# Power.net
KiCad netlist of a schematic drawn in Altium Designer
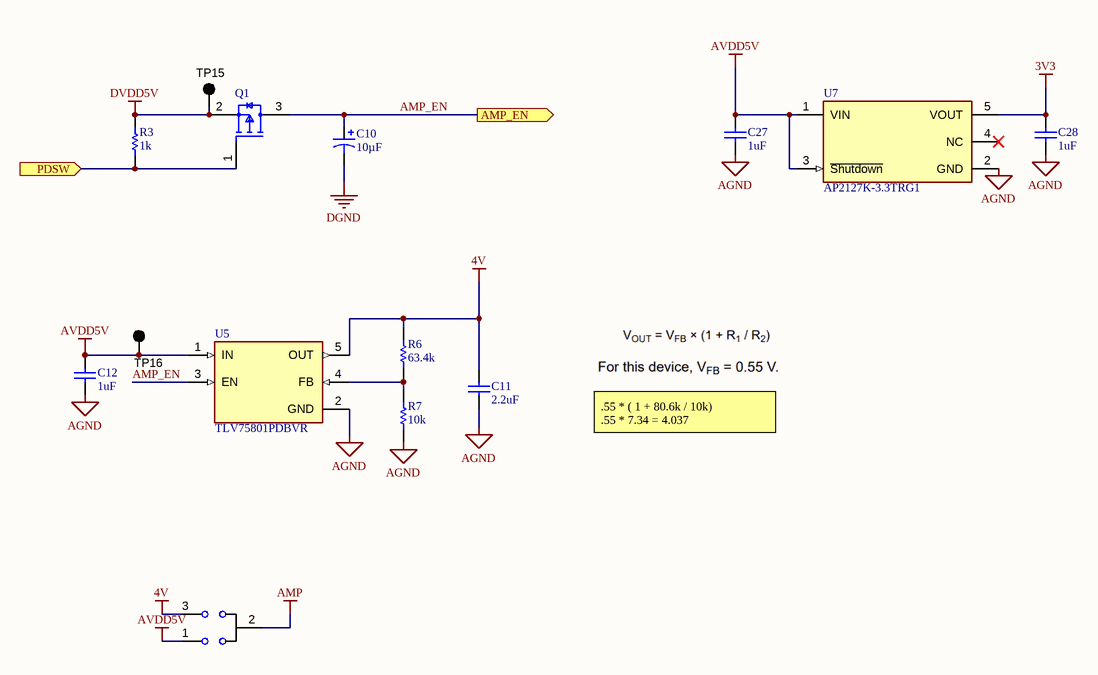
[diagram p0: Power.SchDoc]

(export (version "E")
  (design (tool "Eeschema 10.0.6"))
  (components
    (comp (ref "C10")
      (value "10µF")
      (footprint "1206 TANT CASE A")
      (description "CAP TANT 10UF 16V 20% 1206")
      (fields (field (name "TOLERANCE") "±20%") (field (name "MANUFACTURER") "Kemet"))
      (libsource (lib "SamlibSCH") (part "T491A106M016AT"))
    )
    (comp (ref "C11") (value "2.2uF") (footprint "0603") (libsource (lib "SamlibSCH") (part "C TBD 0603")))
    (comp (ref "C12") (value "1uF") (footprint "0603") (libsource (lib "SamlibSCH") (part "C TBD 0603")))
    (comp (ref "C27") (value "1uF") (footprint "0603") (libsource (lib "SamlibSCH") (part "C TBD 0603")))
    (comp (ref "C28") (value "1uF") (footprint "0603") (libsource (lib "SamlibSCH") (part "C TBD 0603")))
    (comp (ref "JP1")
      (value "2 way jumper")
      (footprint "0603 2 way jumper")
      (libsource (lib "Schlib1") (part "2 way jumper"))
    )
    (comp (ref "Q1")
      (value "DMG2301L-7")
      (footprint "FP-SOT23-MFG")
      (description "MOSFET P-CH 20V 3A SOT23")
      (fields
        (field (name "MANUFACTURER") "Diodes Inc.")
        (field (name "OCTOPART") "https://octopart.com/dmg2301l-7-diodes+inc.-67250456")
      )
      (libsource (lib "Altium Content Vault") (part "b8f99f9e586195791e7fb11725ebaeb"))
    )
    (comp (ref "R3") (value "1k") (footprint "0603") (libsource (lib "SamlibSCH") (part "R TBD 0603")))
    (comp (ref "R6") (value "63.4k") (footprint "0603") (libsource (lib "SamlibSCH") (part "R TBD 0603")))
    (comp (ref "R7") (value "10k") (footprint "0603") (libsource (lib "SamlibSCH") (part "R TBD 0603")))
    (comp (ref "TP15")
      (value "5001")
      (footprint "Testpoint pad")
      (description "TEST POINT PC MINI .040\"D BLACK")
      (fields (field (name "MANUFACTURER") "Keystone Electronics"))
      (libsource (lib "SamlibSCH") (part "5001"))
    )
    (comp (ref "TP16")
      (value "5001")
      (footprint "Testpoint pad")
      (description "TEST POINT PC MINI .040\"D BLACK")
      (fields (field (name "MANUFACTURER") "Keystone Electronics"))
      (libsource (lib "SamlibSCH") (part "5001"))
    )
    (comp (ref "U5")
      (value "TLV75801PDBVR")
      (footprint "SOT95P280X145-5N")
      (description "500-mA, low-IQ, high-accuracy, adjustable ultra-low-dropout voltage regulator with enable")
      (fields (field (name "MF") "Texas Instruments"))
      (libsource (lib "Schlib1") (part "TLV75801PDBVR"))
    )
    (comp (ref "U7")
      (value "AP2127K-3.3TRG1")
      (footprint "FP-SOT25-MFG")
      (description "IC REG LINEAR 3.3V 300MA SOT23-5")
      (fields
        (field (name "MANUFACTURER") "Diodes Inc.")
        (field (name "OCTOPART") "https://octopart.com/ap2127k-3.3trg1-diodes+inc.-30954597")
      )
      (libsource (lib "Altium Content Vault") (part "9cec5dc8377dcc1fea4333fa34f1f58"))
    )
  )
  (nets
    (net (code "1") (name "/AMP_EN") (class "Default")
      (node (ref "C10") (pin "2") (pinfunction "2_2") (pintype "passive"))
      (node (ref "Q1") (pin "3") (pinfunction "D_3") (pintype "passive"))
      (node (ref "U5") (pin "3") (pinfunction "EN_3") (pintype "input"))
    )
    (net (code "2") (name "/PDSW") (class "Default")
      (node (ref "Q1") (pin "1") (pinfunction "G_1") (pintype "passive"))
      (node (ref "R3") (pin "1") (pinfunction "1_1") (pintype "passive"))
    )
    (net (code "3") (name "3V3") (class "Default")
      (node (ref "C28") (pin "2") (pinfunction "2_2") (pintype "passive"))
      (node (ref "U7") (pin "5") (pinfunction "VOUT_5") (pintype "power_in"))
    )
    (net (code "4") (name "4V") (class "Default")
      (node (ref "C11") (pin "2") (pinfunction "2_2") (pintype "passive"))
      (node (ref "JP1") (pin "3") (pinfunction "3_3") (pintype "passive"))
      (node (ref "R6") (pin "2") (pinfunction "2_2") (pintype "passive"))
      (node (ref "U5") (pin "5") (pinfunction "OUT_5") (pintype "output"))
    )
    (net (code "5") (name "AGND") (class "Default")
      (node (ref "C11") (pin "1") (pinfunction "1_1") (pintype "passive"))
      (node (ref "C12") (pin "1") (pinfunction "1_1") (pintype "passive"))
      (node (ref "C27") (pin "1") (pinfunction "1_1") (pintype "passive"))
      (node (ref "C28") (pin "1") (pinfunction "1_1") (pintype "passive"))
      (node (ref "R7") (pin "1") (pinfunction "1_1") (pintype "passive"))
      (node (ref "U5") (pin "2") (pinfunction "GND_2") (pintype "power_in"))
      (node (ref "U7") (pin "2") (pinfunction "GND_2") (pintype "power_in"))
    )
    (net (code "6") (name "AMP") (class "Default")
      (node (ref "JP1") (pin "2") (pinfunction "2_2") (pintype "passive"))
    )
    (net (code "7") (name "AVDD5V") (class "Default")
      (node (ref "C12") (pin "2") (pinfunction "2_2") (pintype "passive"))
      (node (ref "C27") (pin "2") (pinfunction "2_2") (pintype "passive"))
      (node (ref "JP1") (pin "1") (pinfunction "1_1") (pintype "passive"))
      (node (ref "TP16") (pin "1") (pintype "passive"))
      (node (ref "U5") (pin "1") (pinfunction "IN_1") (pintype "input"))
      (node (ref "U7") (pin "1") (pinfunction "VIN_1") (pintype "power_in"))
      (node (ref "U7") (pin "3") (pinfunction "~{Shutdown}_3") (pintype "input"))
    )
    (net (code "8") (name "DGND") (class "Default")
      (node (ref "C10") (pin "1") (pinfunction "1_1") (pintype "passive"))
    )
    (net (code "9") (name "DVDD5V") (class "Default")
      (node (ref "Q1") (pin "2") (pinfunction "S_2") (pintype "passive"))
      (node (ref "R3") (pin "2") (pinfunction "2_2") (pintype "passive"))
      (node (ref "TP15") (pin "1") (pintype "passive"))
    )
    (net (code "10") (name "Net-(U5-FB)") (class "Default")
      (node (ref "R6") (pin "1") (pinfunction "1_1") (pintype "passive"))
      (node (ref "R7") (pin "2") (pinfunction "2_2") (pintype "passive"))
      (node (ref "U5") (pin "4") (pinfunction "FB_4") (pintype "input"))
    )
    (net (code "11") (name "unconnected-(U7-NC-Pad4)") (class "Default")
      (node (ref "U7") (pin "4") (pinfunction "NC_4") (pintype "passive+no_connect"))
    )
  )
)
